# ESP32_Board.net
KiCad netlist of a schematic drawn in Altium Designer
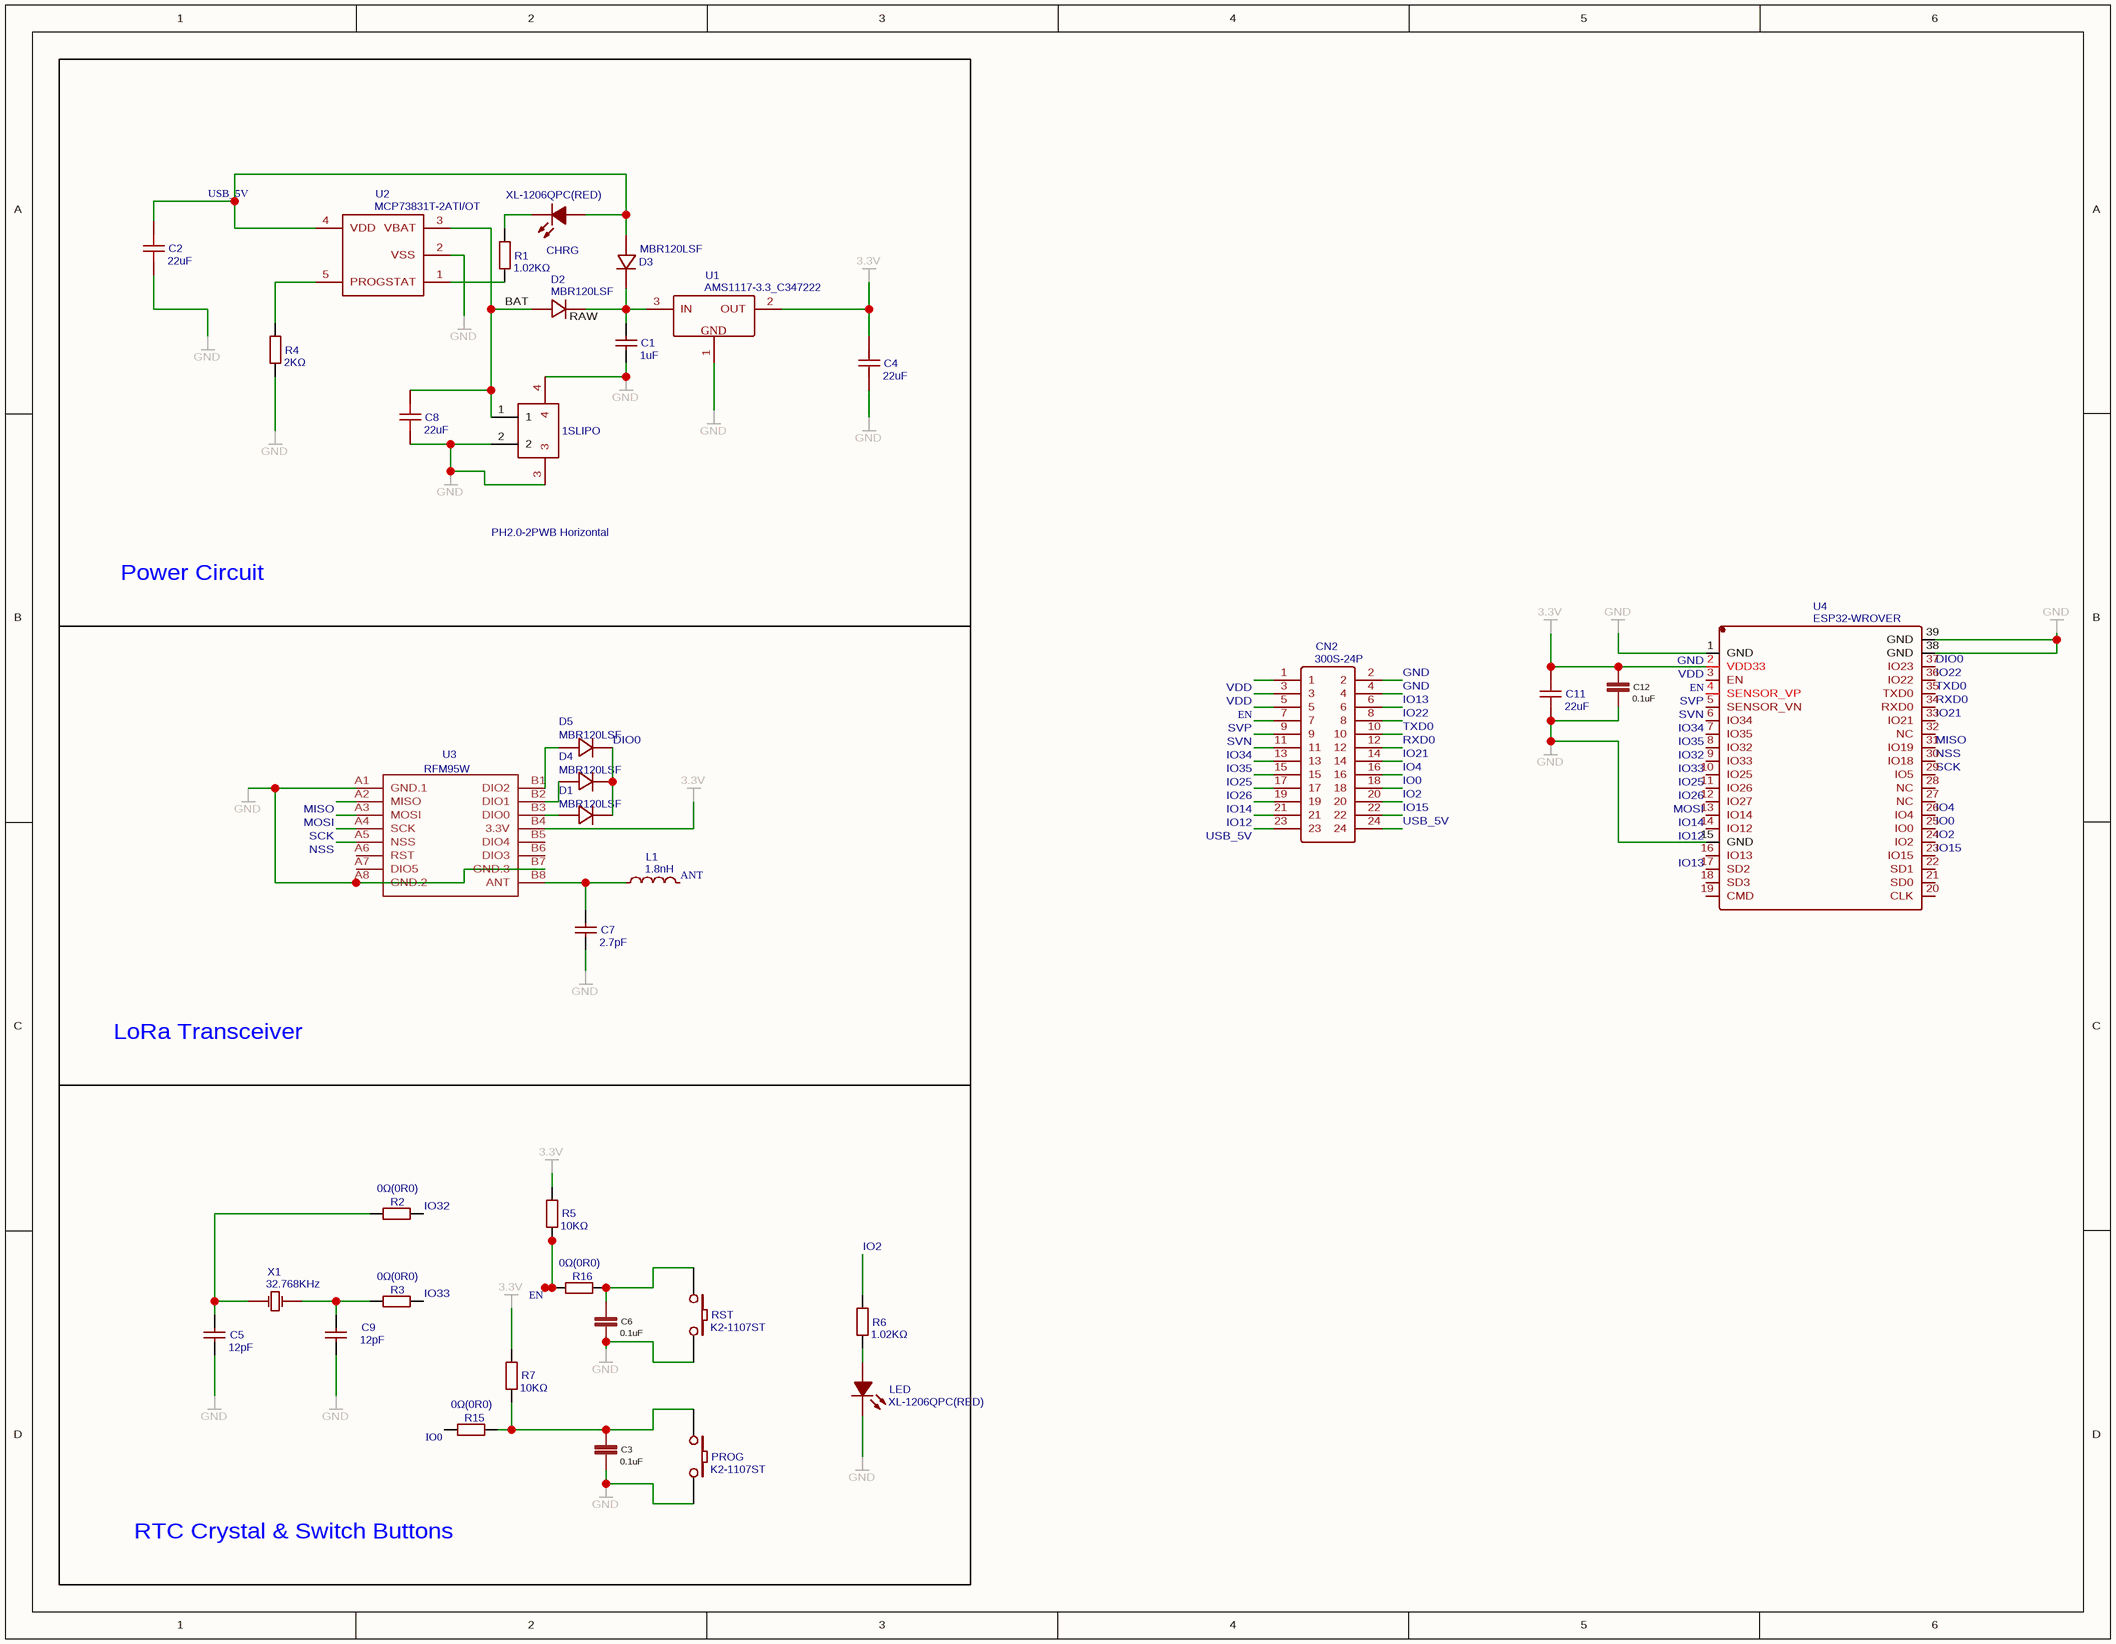
[diagram p0: ESP32+Board.schdoc]

(export (version "E")
  (design (tool "Eeschema 10.0.6"))
  (components
    (comp (ref "1SLIPO")
      (value "PH2.0-2PWB Horizontal")
      (fields (field (name "BOM_SUPPLIER PART") "C47647"))
      (libsource (lib "altium-import") (part "root_3_PH2.0-2PWB Horizontal_"))
    )
    (comp (ref "C1")
      (value "1uF")
      (fields
        (field (name "VOLTAGE") "50V")
        (field (name "TOLERANCE") "±10%")
        (field (name "BOM_MANUFACTURER PART") "0805B105K500NT")
      )
      (libsource (lib "altium-import") (part "root_1_1uF_"))
    )
    (comp (ref "C2")
      (value "22uF")
      (fields
        (field (name "BOM_SUPPLIER PART") "C307563")
        (field (name "BOM_MANUFACTURER PART") "CL21X226MRQNNNE")
        (field (name "CONTRIBUTOR") "LCSC")
      )
      (libsource (lib "altium-import") (part "root_0_22uF_"))
    )
    (comp (ref "C3") (value "0.1uF") (libsource (lib "altium-import") (part "root_0_0.1uF_")))
    (comp (ref "C4")
      (value "22uF")
      (fields
        (field (name "BOM_SUPPLIER PART") "C307563")
        (field (name "BOM_MANUFACTURER PART") "CL21X226MRQNNNE")
        (field (name "CONTRIBUTOR") "LCSC")
      )
      (libsource (lib "altium-import") (part "root_0_22uF_"))
    )
    (comp (ref "C5")
      (value "12pF")
      (fields
        (field (name "BOM_MANUFACTURER PART") "GCM1882C1H120FA01D")
        (field (name "BOM_SUPPLIER PART") "C126539")
      )
      (libsource (lib "altium-import") (part "root_1_12pF_"))
    )
    (comp (ref "C6") (value "0.1uF") (libsource (lib "altium-import") (part "root_0_0.1uF_")))
    (comp (ref "C7")
      (value "2.7pF")
      (fields
        (field (name "BOM_MANUFACTURER PART") "CL10C2R7CB8NNNC")
        (field (name "BOM_SUPPLIER PART") "C16149")
        (field (name "CONTRIBUTOR") "LCSC")
      )
      (libsource (lib "altium-import") (part "root_1_2.7pF_"))
    )
    (comp (ref "C8")
      (value "22uF")
      (fields
        (field (name "BOM_SUPPLIER PART") "C307563")
        (field (name "BOM_MANUFACTURER PART") "CL21X226MRQNNNE")
        (field (name "CONTRIBUTOR") "LCSC")
      )
      (libsource (lib "altium-import") (part "root_0_22uF_"))
    )
    (comp (ref "C9")
      (value "12pF")
      (fields
        (field (name "BOM_MANUFACTURER PART") "GCM1882C1H120FA01D")
        (field (name "BOM_SUPPLIER PART") "C126539")
      )
      (libsource (lib "altium-import") (part "root_1_12pF_"))
    )
    (comp (ref "C11")
      (value "22uF")
      (fields
        (field (name "BOM_SUPPLIER PART") "C307563")
        (field (name "BOM_MANUFACTURER PART") "CL21X226MRQNNNE")
        (field (name "CONTRIBUTOR") "LCSC")
      )
      (libsource (lib "altium-import") (part "root_0_22uF_"))
    )
    (comp (ref "C12") (value "0.1uF") (libsource (lib "altium-import") (part "root_0_0.1uF_")))
    (comp (ref "CHRG")
      (value "XL-1206QPC(RED)")
      (fields (field (name "BOM_MANUFACTURER PART") "XL-1206QPC") (field (name "BOM_SUPPLIER PART") "C10781"))
      (libsource (lib "altium-import") (part "root_2_XL-1206QPC(RED)_"))
    )
    (comp (ref "CN2")
      (value "300S-24P")
      (fields (field (name "BOM_SUPPLIER PART") "C132440") (field (name "CONTRIBUTOR") "LCSC"))
      (libsource (lib "altium-import") (part "root_0_300S-24P_"))
    )
    (comp (ref "D1")
      (value "MBR120LSF")
      (fields (field (name "BOM_SUPPLIER PART") "C130880") (field (name "CONTRIBUTOR") "LCSC"))
      (libsource (lib "altium-import") (part "root_0_MBR120LSF_"))
    )
    (comp (ref "D2")
      (value "MBR120LSF")
      (fields (field (name "BOM_SUPPLIER PART") "C130880") (field (name "CONTRIBUTOR") "LCSC"))
      (libsource (lib "altium-import") (part "root_0_MBR120LSF_"))
    )
    (comp (ref "D3")
      (value "MBR120LSF")
      (fields (field (name "BOM_SUPPLIER PART") "C130880") (field (name "CONTRIBUTOR") "LCSC"))
      (libsource (lib "altium-import") (part "root_3_MBR120LSF_"))
    )
    (comp (ref "D4")
      (value "MBR120LSF")
      (fields (field (name "BOM_SUPPLIER PART") "C130880") (field (name "CONTRIBUTOR") "LCSC"))
      (libsource (lib "altium-import") (part "root_0_MBR120LSF_"))
    )
    (comp (ref "D5")
      (value "MBR120LSF")
      (fields (field (name "BOM_SUPPLIER PART") "C130880") (field (name "CONTRIBUTOR") "LCSC"))
      (libsource (lib "altium-import") (part "root_0_MBR120LSF_"))
    )
    (comp (ref "L1")
      (value "1.8nH")
      (fields
        (field (name "BOM_MANUFACTURER PART") "VHF160808H1N8ST")
        (field (name "BOM_SUPPLIER PART") "C1026")
        (field (name "CONTRIBUTOR") "LCSC")
      )
      (libsource (lib "altium-import") (part "root_0_1.8nH_"))
    )
    (comp (ref "LED")
      (value "XL-1206QPC(RED)")
      (fields (field (name "BOM_MANUFACTURER PART") "XL-1206QPC") (field (name "BOM_SUPPLIER PART") "C10781"))
      (libsource (lib "altium-import") (part "root_3_XL-1206QPC(RED)_"))
    )
    (comp (ref "PROG")
      (value "K2-1107ST")
      (fields (field (name "BOM_SUPPLIER PART") "C118141") (field (name "CONTRIBUTOR") "LCSC"))
      (libsource (lib "altium-import") (part "root_3_K2-1107ST_"))
    )
    (comp (ref "R1")
      (value "1.02KΩ")
      (fields
        (field (name "POWER") "1/8W")
        (field (name "TOLERANCE") "±1%")
        (field (name "BOM_MANUFACTURER PART") "0805W8F1021T5E")
      )
      (libsource (lib "altium-import") (part "root_1_1.02KΩ_"))
    )
    (comp (ref "R2")
      (value "0Ω(0R0)")
      (fields
        (field (name "BOM_MANUFACTURER PART") "CR0603FA0000G")
        (field (name "BOM_SUPPLIER PART") "C100699")
      )
      (libsource (lib "altium-import") (part "root_0_0Ω(0R0)_"))
    )
    (comp (ref "R3")
      (value "0Ω(0R0)")
      (fields
        (field (name "BOM_MANUFACTURER PART") "CR0603FA0000G")
        (field (name "BOM_SUPPLIER PART") "C100699")
      )
      (libsource (lib "altium-import") (part "root_0_0Ω(0R0)_"))
    )
    (comp (ref "R4")
      (value "2KΩ")
      (fields
        (field (name "POWER") "1/8W")
        (field (name "TOLERANCE") "±5%")
        (field (name "BOM_MANUFACTURER PART") "0805W8J0202T5E")
      )
      (libsource (lib "altium-import") (part "root_1_2KΩ_"))
    )
    (comp (ref "R5")
      (value "10KΩ")
      (fields
        (field (name "BOM_MANUFACTURER PART") "0805W8J0103T5E")
        (field (name "BOM_SUPPLIER PART") "C25612")
      )
      (libsource (lib "altium-import") (part "root_1_10KΩ_"))
    )
    (comp (ref "R6")
      (value "1.02KΩ")
      (fields
        (field (name "POWER") "1/8W")
        (field (name "TOLERANCE") "±1%")
        (field (name "BOM_MANUFACTURER PART") "0805W8F1021T5E")
      )
      (libsource (lib "altium-import") (part "root_1_1.02KΩ_"))
    )
    (comp (ref "R7")
      (value "10KΩ")
      (fields
        (field (name "BOM_MANUFACTURER PART") "0805W8J0103T5E")
        (field (name "BOM_SUPPLIER PART") "C25612")
      )
      (libsource (lib "altium-import") (part "root_1_10KΩ_"))
    )
    (comp (ref "R15")
      (value "0Ω(0R0)")
      (fields
        (field (name "BOM_MANUFACTURER PART") "CR0603FA0000G")
        (field (name "BOM_SUPPLIER PART") "C100699")
      )
      (libsource (lib "altium-import") (part "root_0_0Ω(0R0)_"))
    )
    (comp (ref "R16")
      (value "0Ω(0R0)")
      (fields
        (field (name "BOM_MANUFACTURER PART") "CR0603FA0000G")
        (field (name "BOM_SUPPLIER PART") "C100699")
      )
      (libsource (lib "altium-import") (part "root_0_0Ω(0R0)_"))
    )
    (comp (ref "RST")
      (value "K2-1107ST")
      (fields (field (name "BOM_SUPPLIER PART") "C118141") (field (name "CONTRIBUTOR") "LCSC"))
      (libsource (lib "altium-import") (part "root_3_K2-1107ST_"))
    )
    (comp (ref "U1")
      (value "AMS1117-3.3_C347222")
      (fields
        (field (name "BOM_SUPPLIER PART") "C347222")
        (field (name "BOM_MANUFACTURER PART") "AMS1117-3.3")
        (field (name "CONTRIBUTOR") "LCSC")
      )
      (libsource (lib "altium-import") (part "root_0_AMS1117-3.3_C347222_"))
    )
    (comp (ref "U2")
      (value "MCP73831T-2ATI/OT")
      (fields (field (name "BOM_SUPPLIER PART") "C14879") (field (name "CONTRIBUTOR") "LCSC"))
      (libsource (lib "altium-import") (part "root_2_MCP73831T-2ATI/OT_"))
    )
    (comp (ref "U3")
      (value "RFM95W")
      (description "868915 MHz LoRa Radio Transceiver Module based on SX1276 chip")
      (fields
        (field (name "BOM_MANUFACTURER PART") "RFM95W-868S2")
        (field (name "BOM_SUPPLIER PART") "125-1259")
      )
      (libsource (lib "altium-import") (part "root_0_RFM95W_"))
    )
    (comp (ref "U4")
      (value "ESP32-WROVER")
      (fields (field (name "BOM_SUPPLIER PART") "C129145") (field (name "CONTRIBUTOR") "LCSC"))
      (libsource (lib "altium-import") (part "root_0_ESP32-WROVER_"))
    )
    (comp (ref "X1")
      (value "32.768KHz")
      (fields
        (field (name "BOM_MANUFACTURER PART") "YST310S32.768KHz12.5pF10ppm")
        (field (name "BOM_SUPPLIER PART") "C94279")
      )
      (libsource (lib "altium-import") (part "root_2_32.768KHz_"))
    )
  )
  (nets
    (net (code "1") (name "/ANT") (class "Default")
      (node (ref "L1") (pin "2") (pinfunction "2_2") (pintype "passive"))
    )
    (net (code "2") (name "/BAT") (class "Default")
      (node (ref "1SLIPO") (pin "1") (pinfunction "1_1") (pintype "passive"))
      (node (ref "C8") (pin "2") (pinfunction "2_2") (pintype "passive"))
      (node (ref "D2") (pin "2") (pinfunction "A_2") (pintype "passive"))
      (node (ref "U2") (pin "3") (pinfunction "VBAT_3") (pintype "passive"))
    )
    (net (code "3") (name "/DIO0") (class "Default")
      (node (ref "D1") (pin "1") (pinfunction "C_1") (pintype "passive"))
      (node (ref "D4") (pin "1") (pinfunction "C_1") (pintype "passive"))
      (node (ref "D5") (pin "1") (pinfunction "C_1") (pintype "passive"))
      (node (ref "U4") (pin "37") (pinfunction "IO23_37") (pintype "passive"))
    )
    (net (code "4") (name "/EN") (class "Default")
      (node (ref "CN2") (pin "5") (pinfunction "5_5") (pintype "passive"))
      (node (ref "R16") (pin "1") (pinfunction "1_1") (pintype "passive"))
      (node (ref "R5") (pin "1") (pinfunction "1_1") (pintype "passive"))
      (node (ref "U4") (pin "3") (pinfunction "EN_3") (pintype "passive"))
    )
    (net (code "5") (name "/IO0") (class "Default")
      (node (ref "CN2") (pin "18") (pinfunction "18_18") (pintype "passive"))
      (node (ref "R15") (pin "1") (pinfunction "1_1") (pintype "passive"))
      (node (ref "U4") (pin "25") (pinfunction "IO0_25") (pintype "passive"))
    )
    (net (code "6") (name "/IO2") (class "Default")
      (node (ref "CN2") (pin "20") (pinfunction "20_20") (pintype "passive"))
      (node (ref "R6") (pin "2") (pinfunction "2_2") (pintype "passive"))
      (node (ref "U4") (pin "24") (pinfunction "IO2_24") (pintype "passive"))
    )
    (net (code "7") (name "/IO4") (class "Default")
      (node (ref "CN2") (pin "16") (pinfunction "16_16") (pintype "passive"))
      (node (ref "U4") (pin "26") (pinfunction "IO4_26") (pintype "passive"))
    )
    (net (code "8") (name "/IO12") (class "Default")
      (node (ref "CN2") (pin "21") (pinfunction "21_21") (pintype "passive"))
      (node (ref "U4") (pin "14") (pinfunction "IO12_14") (pintype "passive"))
    )
    (net (code "9") (name "/IO13") (class "Default")
      (node (ref "CN2") (pin "6") (pinfunction "6_6") (pintype "passive"))
      (node (ref "U4") (pin "16") (pinfunction "IO13_16") (pintype "passive"))
    )
    (net (code "10") (name "/IO14") (class "Default")
      (node (ref "CN2") (pin "19") (pinfunction "19_19") (pintype "passive"))
      (node (ref "U4") (pin "13") (pinfunction "IO14_13") (pintype "passive"))
    )
    (net (code "11") (name "/IO15") (class "Default")
      (node (ref "CN2") (pin "22") (pinfunction "22_22") (pintype "passive"))
      (node (ref "U4") (pin "23") (pinfunction "IO15_23") (pintype "passive"))
    )
    (net (code "12") (name "/IO21") (class "Default")
      (node (ref "CN2") (pin "14") (pinfunction "14_14") (pintype "passive"))
      (node (ref "U4") (pin "33") (pinfunction "IO21_33") (pintype "passive"))
    )
    (net (code "13") (name "/IO22") (class "Default")
      (node (ref "CN2") (pin "8") (pinfunction "8_8") (pintype "passive"))
      (node (ref "U4") (pin "36") (pinfunction "IO22_36") (pintype "passive"))
    )
    (net (code "14") (name "/IO25") (class "Default")
      (node (ref "CN2") (pin "15") (pinfunction "15_15") (pintype "passive"))
      (node (ref "U4") (pin "10") (pinfunction "IO25_10") (pintype "passive"))
    )
    (net (code "15") (name "/IO26") (class "Default")
      (node (ref "CN2") (pin "17") (pinfunction "17_17") (pintype "passive"))
      (node (ref "U4") (pin "11") (pinfunction "IO26_11") (pintype "passive"))
    )
    (net (code "16") (name "/IO32") (class "Default")
      (node (ref "R2") (pin "2") (pinfunction "2_2") (pintype "passive"))
      (node (ref "U4") (pin "8") (pinfunction "IO32_8") (pintype "passive"))
    )
    (net (code "17") (name "/IO33") (class "Default")
      (node (ref "R3") (pin "2") (pinfunction "2_2") (pintype "passive"))
      (node (ref "U4") (pin "9") (pinfunction "IO33_9") (pintype "passive"))
    )
    (net (code "18") (name "/IO34") (class "Default")
      (node (ref "CN2") (pin "11") (pinfunction "11_11") (pintype "passive"))
      (node (ref "U4") (pin "6") (pinfunction "IO34_6") (pintype "passive"))
    )
    (net (code "19") (name "/IO35") (class "Default")
      (node (ref "CN2") (pin "13") (pinfunction "13_13") (pintype "passive"))
      (node (ref "U4") (pin "7") (pinfunction "IO35_7") (pintype "passive"))
    )
    (net (code "20") (name "/MISO") (class "Default")
      (node (ref "U3") (pin "A2") (pinfunction "MISO_A2") (pintype "passive"))
      (node (ref "U4") (pin "31") (pinfunction "IO19_31") (pintype "passive"))
    )
    (net (code "21") (name "/MOSI") (class "Default")
      (node (ref "U3") (pin "A3") (pinfunction "MOSI_A3") (pintype "passive"))
      (node (ref "U4") (pin "12") (pinfunction "IO27_12") (pintype "passive"))
    )
    (net (code "22") (name "/NSS") (class "Default")
      (node (ref "U3") (pin "A5") (pinfunction "NSS_A5") (pintype "passive"))
      (node (ref "U4") (pin "30") (pinfunction "IO18_30") (pintype "passive"))
    )
    (net (code "23") (name "/RAW") (class "Default")
      (node (ref "C1") (pin "2") (pinfunction "2_2") (pintype "passive"))
      (node (ref "D2") (pin "1") (pinfunction "C_1") (pintype "passive"))
      (node (ref "D3") (pin "1") (pinfunction "C_1") (pintype "passive"))
      (node (ref "U1") (pin "3") (pinfunction "IN_3") (pintype "passive"))
    )
    (net (code "24") (name "/RXD0") (class "Default")
      (node (ref "CN2") (pin "12") (pinfunction "12_12") (pintype "passive"))
      (node (ref "U4") (pin "34") (pinfunction "RXD0_34") (pintype "passive"))
    )
    (net (code "25") (name "/SCK") (class "Default")
      (node (ref "U3") (pin "A4") (pinfunction "SCK_A4") (pintype "passive"))
      (node (ref "U4") (pin "29") (pinfunction "IO5_29") (pintype "passive"))
    )
    (net (code "26") (name "/SVN") (class "Default")
      (node (ref "CN2") (pin "9") (pinfunction "9_9") (pintype "passive"))
      (node (ref "U4") (pin "5") (pinfunction "SENSOR_VN_5") (pintype "passive"))
    )
    (net (code "27") (name "/SVP") (class "Default")
      (node (ref "CN2") (pin "7") (pinfunction "7_7") (pintype "passive"))
      (node (ref "U4") (pin "4") (pinfunction "SENSOR_VP_4") (pintype "passive"))
    )
    (net (code "28") (name "/TXD0") (class "Default")
      (node (ref "CN2") (pin "10") (pinfunction "10_10") (pintype "passive"))
      (node (ref "U4") (pin "35") (pinfunction "TXD0_35") (pintype "passive"))
    )
    (net (code "29") (name "/USB_5V") (class "Default")
      (node (ref "C2") (pin "2") (pinfunction "2_2") (pintype "passive"))
      (node (ref "CHRG") (pin "2") (pinfunction "A_2") (pintype "passive"))
      (node (ref "CN2") (pin "23") (pinfunction "23_23") (pintype "passive"))
      (node (ref "CN2") (pin "24") (pinfunction "24_24") (pintype "passive"))
      (node (ref "D3") (pin "2") (pinfunction "A_2") (pintype "passive"))
      (node (ref "U2") (pin "4") (pinfunction "VDD_4") (pintype "passive"))
    )
    (net (code "30") (name "3.3V") (class "Default")
      (node (ref "C11") (pin "2") (pinfunction "2_2") (pintype "passive"))
      (node (ref "C12") (pin "1") (pinfunction "1_1") (pintype "passive"))
      (node (ref "C4") (pin "2") (pinfunction "2_2") (pintype "passive"))
      (node (ref "CN2") (pin "1") (pinfunction "1_1") (pintype "passive"))
      (node (ref "CN2") (pin "3") (pinfunction "3_3") (pintype "passive"))
      (node (ref "R5") (pin "2") (pinfunction "2_2") (pintype "passive"))
      (node (ref "R7") (pin "2") (pinfunction "2_2") (pintype "passive"))
      (node (ref "U1") (pin "2") (pinfunction "OUT_2") (pintype "passive"))
      (node (ref "U3") (pin "B4") (pinfunction "3.3V_B4") (pintype "passive"))
      (node (ref "U4") (pin "2") (pinfunction "VDD33_2") (pintype "passive"))
    )
    (net (code "31") (name "GND") (class "Default")
      (node (ref "1SLIPO") (pin "2") (pinfunction "2_2") (pintype "passive"))
      (node (ref "1SLIPO") (pin "3") (pinfunction "3_3") (pintype "passive"))
      (node (ref "1SLIPO") (pin "4") (pinfunction "4_4") (pintype "passive"))
      (node (ref "C1") (pin "1") (pinfunction "1_1") (pintype "passive"))
      (node (ref "C11") (pin "1") (pinfunction "1_1") (pintype "passive"))
      (node (ref "C12") (pin "2") (pinfunction "2_2") (pintype "passive"))
      (node (ref "C2") (pin "1") (pinfunction "1_1") (pintype "passive"))
      (node (ref "C3") (pin "2") (pinfunction "2_2") (pintype "passive"))
      (node (ref "C4") (pin "1") (pinfunction "1_1") (pintype "passive"))
      (node (ref "C5") (pin "1") (pinfunction "1_1") (pintype "passive"))
      (node (ref "C6") (pin "2") (pinfunction "2_2") (pintype "passive"))
      (node (ref "C7") (pin "1") (pinfunction "1_1") (pintype "passive"))
      (node (ref "C8") (pin "1") (pinfunction "1_1") (pintype "passive"))
      (node (ref "C9") (pin "1") (pinfunction "1_1") (pintype "passive"))
      (node (ref "CN2") (pin "2") (pinfunction "2_2") (pintype "passive"))
      (node (ref "CN2") (pin "4") (pinfunction "4_4") (pintype "passive"))
      (node (ref "LED") (pin "1") (pinfunction "K_1") (pintype "passive"))
      (node (ref "PROG") (pin "2") (pinfunction "2_2") (pintype "passive"))
      (node (ref "R4") (pin "1") (pinfunction "1_1") (pintype "passive"))
      (node (ref "RST") (pin "2") (pinfunction "2_2") (pintype "passive"))
      (node (ref "U1") (pin "1") (pinfunction "ADJ_1") (pintype "passive"))
      (node (ref "U2") (pin "2") (pinfunction "VSS_2") (pintype "passive"))
      (node (ref "U3") (pin "A1") (pinfunction "GND.1_A1") (pintype "passive"))
      (node (ref "U3") (pin "A8") (pinfunction "GND.2_A8") (pintype "passive"))
      (node (ref "U3") (pin "B7") (pinfunction "GND.3_B7") (pintype "passive"))
      (node (ref "U4") (pin "1") (pinfunction "GND_1") (pintype "passive"))
      (node (ref "U4") (pin "15") (pinfunction "GND_15") (pintype "passive"))
      (node (ref "U4") (pin "38") (pinfunction "GND_38") (pintype "passive"))
      (node (ref "U4") (pin "39") (pinfunction "GND_39") (pintype "passive"))
    )
    (net (code "32") (name "Net-(C3-Pad1)") (class "Default")
      (node (ref "C3") (pin "1") (pinfunction "1_1") (pintype "passive"))
      (node (ref "PROG") (pin "1") (pinfunction "1_1") (pintype "passive"))
      (node (ref "R15") (pin "2") (pinfunction "2_2") (pintype "passive"))
      (node (ref "R7") (pin "1") (pinfunction "1_1") (pintype "passive"))
    )
    (net (code "33") (name "Net-(C6-Pad1)") (class "Default")
      (node (ref "C6") (pin "1") (pinfunction "1_1") (pintype "passive"))
      (node (ref "R16") (pin "2") (pinfunction "2_2") (pintype "passive"))
      (node (ref "RST") (pin "1") (pinfunction "1_1") (pintype "passive"))
    )
    (net (code "34") (name "Net-(CHRG-K)") (class "Default")
      (node (ref "CHRG") (pin "1") (pinfunction "K_1") (pintype "passive"))
      (node (ref "R1") (pin "2") (pinfunction "2_2") (pintype "passive"))
    )
    (net (code "35") (name "Net-(D1-A)") (class "Default")
      (node (ref "D1") (pin "2") (pinfunction "A_2") (pintype "passive"))
      (node (ref "U3") (pin "B3") (pinfunction "DIO0_B3") (pintype "passive"))
    )
    (net (code "36") (name "Net-(D4-A)") (class "Default")
      (node (ref "D4") (pin "2") (pinfunction "A_2") (pintype "passive"))
      (node (ref "U3") (pin "B2") (pinfunction "DIO1_B2") (pintype "passive"))
    )
    (net (code "37") (name "Net-(D5-A)") (class "Default")
      (node (ref "D5") (pin "2") (pinfunction "A_2") (pintype "passive"))
      (node (ref "U3") (pin "B1") (pinfunction "DIO2_B1") (pintype "passive"))
    )
    (net (code "38") (name "Net-(LED-A)") (class "Default")
      (node (ref "LED") (pin "2") (pinfunction "A_2") (pintype "passive"))
      (node (ref "R6") (pin "1") (pinfunction "1_1") (pintype "passive"))
    )
    (net (code "39") (name "Net-(U2-PROG)") (class "Default")
      (node (ref "R4") (pin "2") (pinfunction "2_2") (pintype "passive"))
      (node (ref "U2") (pin "5") (pinfunction "PROG_5") (pintype "passive"))
    )
    (net (code "40") (name "Net-(U2-STAT)") (class "Default")
      (node (ref "R1") (pin "1") (pinfunction "1_1") (pintype "passive"))
      (node (ref "U2") (pin "1") (pinfunction "STAT_1") (pintype "passive"))
    )
    (net (code "41") (name "Net-(U3-ANT)") (class "Default")
      (node (ref "C7") (pin "2") (pinfunction "2_2") (pintype "passive"))
      (node (ref "L1") (pin "1") (pinfunction "1_1") (pintype "passive"))
      (node (ref "U3") (pin "B8") (pinfunction "ANT_B8") (pintype "passive"))
    )
    (net (code "42") (name "Net-(X1-OSC1)") (class "Default")
      (node (ref "C9") (pin "2") (pinfunction "2_2") (pintype "passive"))
      (node (ref "R3") (pin "1") (pinfunction "1_1") (pintype "passive"))
      (node (ref "X1") (pin "1") (pinfunction "OSC1_1") (pintype "passive"))
    )
    (net (code "43") (name "Net-(X1-OSC2)") (class "Default")
      (node (ref "C5") (pin "2") (pinfunction "2_2") (pintype "passive"))
      (node (ref "R2") (pin "1") (pinfunction "1_1") (pintype "passive"))
      (node (ref "X1") (pin "2") (pinfunction "OSC2_2") (pintype "passive"))
    )
    (net (code "44") (name "unconnected-(U3-DIO3-PadB6)") (class "Default")
      (node (ref "U3") (pin "B6") (pinfunction "DIO3_B6") (pintype "passive"))
    )
    (net (code "45") (name "unconnected-(U3-DIO4-PadB5)") (class "Default")
      (node (ref "U3") (pin "B5") (pinfunction "DIO4_B5") (pintype "passive"))
    )
    (net (code "46") (name "unconnected-(U3-DIO5-PadA7)") (class "Default")
      (node (ref "U3") (pin "A7") (pinfunction "DIO5_A7") (pintype "passive"))
    )
    (net (code "47") (name "unconnected-(U3-RST-PadA6)") (class "Default")
      (node (ref "U3") (pin "A6") (pinfunction "RST_A6") (pintype "passive"))
    )
    (net (code "48") (name "unconnected-(U4-CLK-Pad20)") (class "Default")
      (node (ref "U4") (pin "20") (pinfunction "CLK_20") (pintype "passive"))
    )
    (net (code "49") (name "unconnected-(U4-CMD-Pad19)") (class "Default")
      (node (ref "U4") (pin "19") (pinfunction "CMD_19") (pintype "passive"))
    )
    (net (code "50") (name "unconnected-(U4-NC-Pad27)") (class "Default")
      (node (ref "U4") (pin "27") (pinfunction "NC_27") (pintype "passive"))
    )
    (net (code "51") (name "unconnected-(U4-NC-Pad28)") (class "Default")
      (node (ref "U4") (pin "28") (pinfunction "NC_28") (pintype "passive"))
    )
    (net (code "52") (name "unconnected-(U4-NC-Pad32)") (class "Default")
      (node (ref "U4") (pin "32") (pinfunction "NC_32") (pintype "passive"))
    )
    (net (code "53") (name "unconnected-(U4-SD0-Pad21)") (class "Default")
      (node (ref "U4") (pin "21") (pinfunction "SD0_21") (pintype "passive"))
    )
    (net (code "54") (name "unconnected-(U4-SD1-Pad22)") (class "Default")
      (node (ref "U4") (pin "22") (pinfunction "SD1_22") (pintype "passive"))
    )
    (net (code "55") (name "unconnected-(U4-SD2-Pad17)") (class "Default")
      (node (ref "U4") (pin "17") (pinfunction "SD2_17") (pintype "passive"))
    )
    (net (code "56") (name "unconnected-(U4-SD3-Pad18)") (class "Default")
      (node (ref "U4") (pin "18") (pinfunction "SD3_18") (pintype "passive"))
    )
  )
)
